# Power.net
KiCad netlist of a schematic drawn in Altium Designer
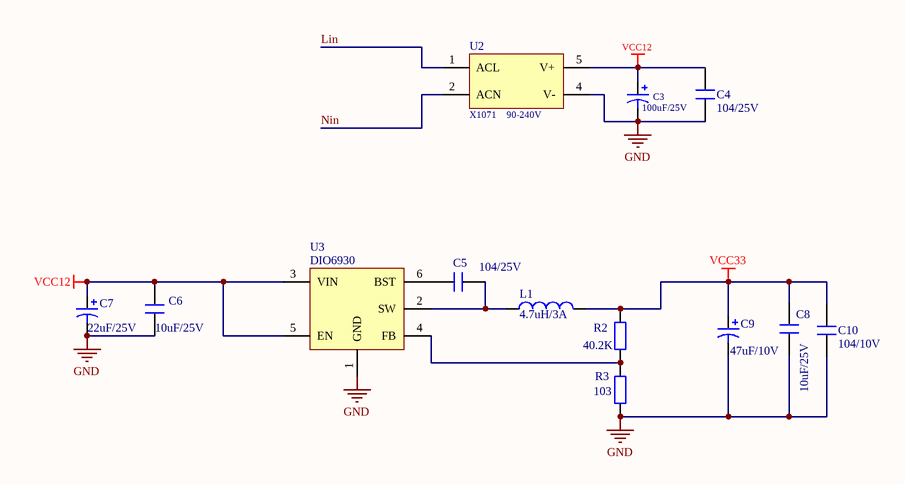
[diagram p0: Power.SchDoc]

(export (version "E")
  (design (tool "Eeschema 10.0.6"))
  (components
    (comp (ref "C3")
      (value "100uF/25V")
      (footprint "CAPPIND06")
      (description "Polarized Capacitor (Radial)")
      (fields (field (name "PUBLISHER") "Altium Limited"))
      (libsource (lib "Miscellaneous Devices") (part "Cap Pol1"))
    )
    (comp (ref "C4") (value "104/25V") (footprint "0603R") (libsource (lib "ES_Schematic") (part "CAP_1")))
    (comp (ref "C5") (value "104/25V") (footprint "0603R") (libsource (lib "ES_Schematic") (part "CAP_1")))
    (comp (ref "C6") (value "10uF/25V") (footprint "0603R") (libsource (lib "ES_Schematic") (part "CAP")))
    (comp (ref "C7")
      (value "22uF/25V")
      (footprint "0805R")
      (description "Polarized Capacitor (Radial)")
      (fields (field (name "PUBLISHER") "Altium Limited"))
      (libsource (lib "Miscellaneous Devices") (part "Cap Pol1"))
    )
    (comp (ref "C8") (value "10uF/25V") (footprint "0603R") (libsource (lib "ES_Schematic") (part "CAP")))
    (comp (ref "C9")
      (value "47uF/10V")
      (footprint "0805R")
      (description "Polarized Capacitor (Radial)")
      (fields (field (name "PUBLISHER") "Altium Limited"))
      (libsource (lib "Miscellaneous Devices") (part "Cap Pol1"))
    )
    (comp (ref "C10") (value "104/10V") (footprint "0603R") (libsource (lib "ES_Schematic") (part "CAP_1")))
    (comp (ref "L1")
      (value "4.7uH/3A")
      (footprint "贴片电感5020")
      (description "Inductor")
      (fields (field (name "PUBLISHER") "Altium Limited"))
      (libsource (lib "Miscellaneous Devices") (part "Inductor"))
    )
    (comp (ref "R2")
      (value "40.2K")
      (footprint "0603R")
      (description "Resistor")
      (fields (field (name "PUBLISHER") "Altium Limited"))
      (libsource (lib "Miscellaneous Devices") (part "Res2"))
    )
    (comp (ref "R3")
      (value "103")
      (footprint "0603R")
      (description "Resistor")
      (fields (field (name "PUBLISHER") "Altium Limited"))
      (libsource (lib "Miscellaneous Devices") (part "Res2"))
    )
    (comp (ref "U2")
      (value "X1071    90-240V")
      (footprint "X1071")
      (libsource (lib "sangjian") (part "AD2DC_EMC"))
    )
    (comp (ref "U3")
      (value "DIO6930")
      (footprint "SOT-23-6DBV")
      (libsource (lib "ES_Schematic") (part "BL8032"))
    )
  )
  (nets
    (net (code "1") (name "/Lin") (class "Default")
      (node (ref "U2") (pin "1") (pinfunction "ACL_1") (pintype "passive"))
    )
    (net (code "2") (name "/Nin") (class "Default")
      (node (ref "U2") (pin "2") (pinfunction "ACN_2") (pintype "passive"))
    )
    (net (code "3") (name "GND") (class "Default")
      (node (ref "C10") (pin "1") (pinfunction "1_1") (pintype "passive"))
      (node (ref "C3") (pin "2") (pinfunction "2_2") (pintype "passive"))
      (node (ref "C4") (pin "1") (pinfunction "1_1") (pintype "passive"))
      (node (ref "C6") (pin "1") (pinfunction "1_1") (pintype "passive"))
      (node (ref "C7") (pin "2") (pinfunction "2_2") (pintype "passive"))
      (node (ref "C8") (pin "1") (pinfunction "1_1") (pintype "passive"))
      (node (ref "C9") (pin "2") (pinfunction "2_2") (pintype "passive"))
      (node (ref "R3") (pin "2") (pinfunction "2_2") (pintype "passive"))
      (node (ref "U2") (pin "4") (pinfunction "V-_4") (pintype "passive"))
      (node (ref "U3") (pin "1") (pinfunction "GND_1") (pintype "passive"))
    )
    (net (code "4") (name "Net-(U3-BST)") (class "Default")
      (node (ref "C5") (pin "2") (pinfunction "2_2") (pintype "passive"))
      (node (ref "U3") (pin "6") (pinfunction "BST_6") (pintype "passive"))
    )
    (net (code "5") (name "Net-(U3-FB)") (class "Default")
      (node (ref "R2") (pin "2") (pinfunction "2_2") (pintype "passive"))
      (node (ref "R3") (pin "1") (pinfunction "1_1") (pintype "passive"))
      (node (ref "U3") (pin "4") (pinfunction "FB_4") (pintype "passive"))
    )
    (net (code "6") (name "Net-(U3-SW)") (class "Default")
      (node (ref "C5") (pin "1") (pinfunction "1_1") (pintype "passive"))
      (node (ref "L1") (pin "1") (pinfunction "1_1") (pintype "passive"))
      (node (ref "U3") (pin "2") (pinfunction "SW_2") (pintype "passive"))
    )
    (net (code "7") (name "VCC12") (class "Default")
      (node (ref "C3") (pin "1") (pinfunction "1_1") (pintype "passive"))
      (node (ref "C4") (pin "2") (pinfunction "2_2") (pintype "passive"))
      (node (ref "C6") (pin "2") (pinfunction "2_2") (pintype "passive"))
      (node (ref "C7") (pin "1") (pinfunction "1_1") (pintype "passive"))
      (node (ref "U2") (pin "5") (pinfunction "V+_5") (pintype "passive"))
      (node (ref "U3") (pin "3") (pinfunction "VIN_3") (pintype "passive"))
      (node (ref "U3") (pin "5") (pinfunction "EN_5") (pintype "passive"))
    )
    (net (code "8") (name "VCC33") (class "Default")
      (node (ref "C10") (pin "2") (pinfunction "2_2") (pintype "passive"))
      (node (ref "C8") (pin "2") (pinfunction "2_2") (pintype "passive"))
      (node (ref "C9") (pin "1") (pinfunction "1_1") (pintype "passive"))
      (node (ref "L1") (pin "2") (pinfunction "2_2") (pintype "passive"))
      (node (ref "R2") (pin "1") (pinfunction "1_1") (pintype "passive"))
    )
  )
)
